# LEDS.net
KiCad netlist of a schematic drawn in Altium Designer
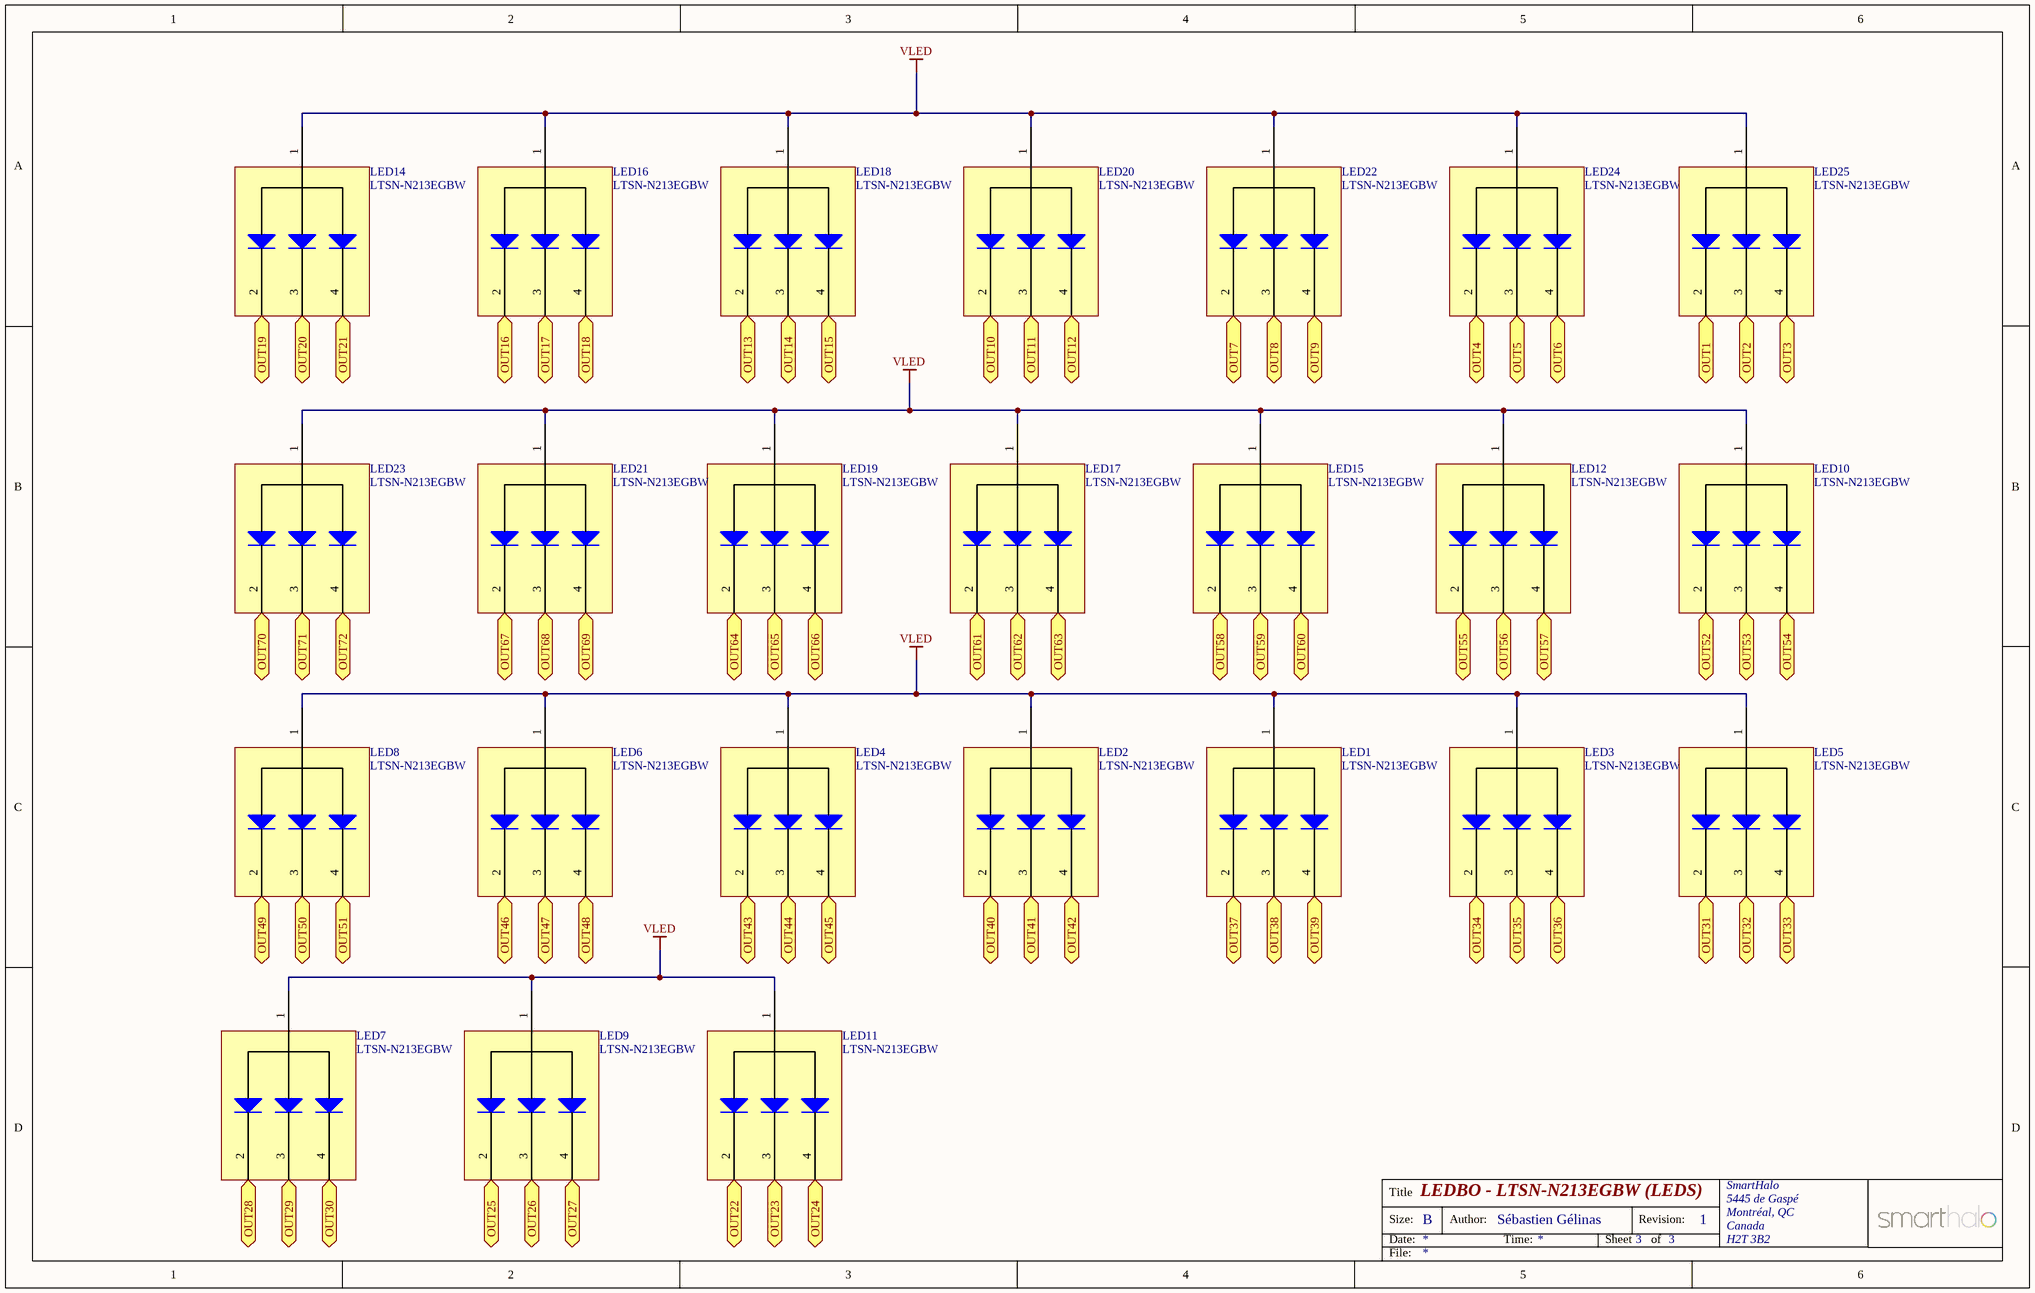
[diagram p0: LEDS.SchDoc]

(export (version "E")
  (design (tool "Eeschema 10.0.6"))
  (components
    (comp (ref "LED1")
      (value "LTSN-N213EGBW")
      (footprint "LTSN-N213EGBW")
      (description "LED SMD LTSN-N213EGBW")
      (fields (field (name "MANUFACTURER") "LiteOn"))
      (libsource (lib "SmartHalo") (part "LTSN-N213EGBW"))
    )
    (comp (ref "LED2")
      (value "LTSN-N213EGBW")
      (footprint "LTSN-N213EGBW")
      (description "LED SMD LTSN-N213EGBW")
      (fields (field (name "MANUFACTURER") "LiteOn"))
      (libsource (lib "SmartHalo") (part "LTSN-N213EGBW"))
    )
    (comp (ref "LED3")
      (value "LTSN-N213EGBW")
      (footprint "LTSN-N213EGBW")
      (description "LED SMD LTSN-N213EGBW")
      (fields (field (name "MANUFACTURER") "LiteOn"))
      (libsource (lib "SmartHalo") (part "LTSN-N213EGBW"))
    )
    (comp (ref "LED4")
      (value "LTSN-N213EGBW")
      (footprint "LTSN-N213EGBW")
      (description "LED SMD LTSN-N213EGBW")
      (fields (field (name "MANUFACTURER") "LiteOn"))
      (libsource (lib "SmartHalo") (part "LTSN-N213EGBW"))
    )
    (comp (ref "LED5")
      (value "LTSN-N213EGBW")
      (footprint "LTSN-N213EGBW")
      (description "LED SMD LTSN-N213EGBW")
      (fields (field (name "MANUFACTURER") "LiteOn"))
      (libsource (lib "SmartHalo") (part "LTSN-N213EGBW"))
    )
    (comp (ref "LED6")
      (value "LTSN-N213EGBW")
      (footprint "LTSN-N213EGBW")
      (description "LED SMD LTSN-N213EGBW")
      (fields (field (name "MANUFACTURER") "LiteOn"))
      (libsource (lib "SmartHalo") (part "LTSN-N213EGBW"))
    )
    (comp (ref "LED7")
      (value "LTSN-N213EGBW")
      (footprint "LTSN-N213EGBW")
      (description "LED SMD LTSN-N213EGBW")
      (fields (field (name "MANUFACTURER") "LiteOn"))
      (libsource (lib "SmartHalo") (part "LTSN-N213EGBW"))
    )
    (comp (ref "LED8")
      (value "LTSN-N213EGBW")
      (footprint "LTSN-N213EGBW")
      (description "LED SMD LTSN-N213EGBW")
      (fields (field (name "MANUFACTURER") "LiteOn"))
      (libsource (lib "SmartHalo") (part "LTSN-N213EGBW"))
    )
    (comp (ref "LED9")
      (value "LTSN-N213EGBW")
      (footprint "LTSN-N213EGBW")
      (description "LED SMD LTSN-N213EGBW")
      (fields (field (name "MANUFACTURER") "LiteOn"))
      (libsource (lib "SmartHalo") (part "LTSN-N213EGBW"))
    )
    (comp (ref "LED10")
      (value "LTSN-N213EGBW")
      (footprint "LTSN-N213EGBW")
      (description "LED SMD LTSN-N213EGBW")
      (fields (field (name "MANUFACTURER") "LiteOn"))
      (libsource (lib "SmartHalo") (part "LTSN-N213EGBW"))
    )
    (comp (ref "LED11")
      (value "LTSN-N213EGBW")
      (footprint "LTSN-N213EGBW")
      (description "LED SMD LTSN-N213EGBW")
      (fields (field (name "MANUFACTURER") "LiteOn"))
      (libsource (lib "SmartHalo") (part "LTSN-N213EGBW"))
    )
    (comp (ref "LED12")
      (value "LTSN-N213EGBW")
      (footprint "LTSN-N213EGBW")
      (description "LED SMD LTSN-N213EGBW")
      (fields (field (name "MANUFACTURER") "LiteOn"))
      (libsource (lib "SmartHalo") (part "LTSN-N213EGBW"))
    )
    (comp (ref "LED14")
      (value "LTSN-N213EGBW")
      (footprint "LTSN-N213EGBW")
      (description "LED SMD LTSN-N213EGBW")
      (fields (field (name "MANUFACTURER") "LiteOn"))
      (libsource (lib "SmartHalo") (part "LTSN-N213EGBW"))
    )
    (comp (ref "LED15")
      (value "LTSN-N213EGBW")
      (footprint "LTSN-N213EGBW")
      (description "LED SMD LTSN-N213EGBW")
      (fields (field (name "MANUFACTURER") "LiteOn"))
      (libsource (lib "SmartHalo") (part "LTSN-N213EGBW"))
    )
    (comp (ref "LED16")
      (value "LTSN-N213EGBW")
      (footprint "LTSN-N213EGBW")
      (description "LED SMD LTSN-N213EGBW")
      (fields (field (name "MANUFACTURER") "LiteOn"))
      (libsource (lib "SmartHalo") (part "LTSN-N213EGBW"))
    )
    (comp (ref "LED17")
      (value "LTSN-N213EGBW")
      (footprint "LTSN-N213EGBW")
      (description "LED SMD LTSN-N213EGBW")
      (fields (field (name "MANUFACTURER") "LiteOn"))
      (libsource (lib "SmartHalo") (part "LTSN-N213EGBW"))
    )
    (comp (ref "LED18")
      (value "LTSN-N213EGBW")
      (footprint "LTSN-N213EGBW")
      (description "LED SMD LTSN-N213EGBW")
      (fields (field (name "MANUFACTURER") "LiteOn"))
      (libsource (lib "SmartHalo") (part "LTSN-N213EGBW"))
    )
    (comp (ref "LED19")
      (value "LTSN-N213EGBW")
      (footprint "LTSN-N213EGBW")
      (description "LED SMD LTSN-N213EGBW")
      (fields (field (name "MANUFACTURER") "LiteOn"))
      (libsource (lib "SmartHalo") (part "LTSN-N213EGBW"))
    )
    (comp (ref "LED20")
      (value "LTSN-N213EGBW")
      (footprint "LTSN-N213EGBW")
      (description "LED SMD LTSN-N213EGBW")
      (fields (field (name "MANUFACTURER") "LiteOn"))
      (libsource (lib "SmartHalo") (part "LTSN-N213EGBW"))
    )
    (comp (ref "LED21")
      (value "LTSN-N213EGBW")
      (footprint "LTSN-N213EGBW")
      (description "LED SMD LTSN-N213EGBW")
      (fields (field (name "MANUFACTURER") "LiteOn"))
      (libsource (lib "SmartHalo") (part "LTSN-N213EGBW"))
    )
    (comp (ref "LED22")
      (value "LTSN-N213EGBW")
      (footprint "LTSN-N213EGBW")
      (description "LED SMD LTSN-N213EGBW")
      (fields (field (name "MANUFACTURER") "LiteOn"))
      (libsource (lib "SmartHalo") (part "LTSN-N213EGBW"))
    )
    (comp (ref "LED23")
      (value "LTSN-N213EGBW")
      (footprint "LTSN-N213EGBW")
      (description "LED SMD LTSN-N213EGBW")
      (fields (field (name "MANUFACTURER") "LiteOn"))
      (libsource (lib "SmartHalo") (part "LTSN-N213EGBW"))
    )
    (comp (ref "LED24")
      (value "LTSN-N213EGBW")
      (footprint "LTSN-N213EGBW")
      (description "LED SMD LTSN-N213EGBW")
      (fields (field (name "MANUFACTURER") "LiteOn"))
      (libsource (lib "SmartHalo") (part "LTSN-N213EGBW"))
    )
    (comp (ref "LED25")
      (value "LTSN-N213EGBW")
      (footprint "LTSN-N213EGBW")
      (description "LED SMD LTSN-N213EGBW")
      (fields (field (name "MANUFACTURER") "LiteOn"))
      (libsource (lib "SmartHalo") (part "LTSN-N213EGBW"))
    )
  )
  (nets
    (net (code "1") (name "/OUT1") (class "Default")
      (node (ref "LED25") (pin "2") (pinfunction "Cathode_Red_2") (pintype "passive"))
    )
    (net (code "2") (name "/OUT2") (class "Default")
      (node (ref "LED25") (pin "3") (pinfunction "Cathode_Green_3") (pintype "passive"))
    )
    (net (code "3") (name "/OUT3") (class "Default")
      (node (ref "LED25") (pin "4") (pinfunction "Cathode_Blue_4") (pintype "passive"))
    )
    (net (code "4") (name "/OUT4") (class "Default")
      (node (ref "LED24") (pin "2") (pinfunction "Cathode_Red_2") (pintype "passive"))
    )
    (net (code "5") (name "/OUT5") (class "Default")
      (node (ref "LED24") (pin "3") (pinfunction "Cathode_Green_3") (pintype "passive"))
    )
    (net (code "6") (name "/OUT6") (class "Default")
      (node (ref "LED24") (pin "4") (pinfunction "Cathode_Blue_4") (pintype "passive"))
    )
    (net (code "7") (name "/OUT7") (class "Default")
      (node (ref "LED22") (pin "2") (pinfunction "Cathode_Red_2") (pintype "passive"))
    )
    (net (code "8") (name "/OUT8") (class "Default")
      (node (ref "LED22") (pin "3") (pinfunction "Cathode_Green_3") (pintype "passive"))
    )
    (net (code "9") (name "/OUT9") (class "Default")
      (node (ref "LED22") (pin "4") (pinfunction "Cathode_Blue_4") (pintype "passive"))
    )
    (net (code "10") (name "/OUT10") (class "Default")
      (node (ref "LED20") (pin "2") (pinfunction "Cathode_Red_2") (pintype "passive"))
    )
    (net (code "11") (name "/OUT11") (class "Default")
      (node (ref "LED20") (pin "3") (pinfunction "Cathode_Green_3") (pintype "passive"))
    )
    (net (code "12") (name "/OUT12") (class "Default")
      (node (ref "LED20") (pin "4") (pinfunction "Cathode_Blue_4") (pintype "passive"))
    )
    (net (code "13") (name "/OUT13") (class "Default")
      (node (ref "LED18") (pin "2") (pinfunction "Cathode_Red_2") (pintype "passive"))
    )
    (net (code "14") (name "/OUT14") (class "Default")
      (node (ref "LED18") (pin "3") (pinfunction "Cathode_Green_3") (pintype "passive"))
    )
    (net (code "15") (name "/OUT15") (class "Default")
      (node (ref "LED18") (pin "4") (pinfunction "Cathode_Blue_4") (pintype "passive"))
    )
    (net (code "16") (name "/OUT16") (class "Default")
      (node (ref "LED16") (pin "2") (pinfunction "Cathode_Red_2") (pintype "passive"))
    )
    (net (code "17") (name "/OUT17") (class "Default")
      (node (ref "LED16") (pin "3") (pinfunction "Cathode_Green_3") (pintype "passive"))
    )
    (net (code "18") (name "/OUT18") (class "Default")
      (node (ref "LED16") (pin "4") (pinfunction "Cathode_Blue_4") (pintype "passive"))
    )
    (net (code "19") (name "/OUT19") (class "Default")
      (node (ref "LED14") (pin "2") (pinfunction "Cathode_Red_2") (pintype "passive"))
    )
    (net (code "20") (name "/OUT20") (class "Default")
      (node (ref "LED14") (pin "3") (pinfunction "Cathode_Green_3") (pintype "passive"))
    )
    (net (code "21") (name "/OUT21") (class "Default")
      (node (ref "LED14") (pin "4") (pinfunction "Cathode_Blue_4") (pintype "passive"))
    )
    (net (code "22") (name "/OUT22") (class "Default")
      (node (ref "LED11") (pin "2") (pinfunction "Cathode_Red_2") (pintype "passive"))
    )
    (net (code "23") (name "/OUT23") (class "Default")
      (node (ref "LED11") (pin "3") (pinfunction "Cathode_Green_3") (pintype "passive"))
    )
    (net (code "24") (name "/OUT24") (class "Default")
      (node (ref "LED11") (pin "4") (pinfunction "Cathode_Blue_4") (pintype "passive"))
    )
    (net (code "25") (name "/OUT25") (class "Default")
      (node (ref "LED9") (pin "2") (pinfunction "Cathode_Red_2") (pintype "passive"))
    )
    (net (code "26") (name "/OUT26") (class "Default")
      (node (ref "LED9") (pin "3") (pinfunction "Cathode_Green_3") (pintype "passive"))
    )
    (net (code "27") (name "/OUT27") (class "Default")
      (node (ref "LED9") (pin "4") (pinfunction "Cathode_Blue_4") (pintype "passive"))
    )
    (net (code "28") (name "/OUT28") (class "Default")
      (node (ref "LED7") (pin "2") (pinfunction "Cathode_Red_2") (pintype "passive"))
    )
    (net (code "29") (name "/OUT29") (class "Default")
      (node (ref "LED7") (pin "3") (pinfunction "Cathode_Green_3") (pintype "passive"))
    )
    (net (code "30") (name "/OUT30") (class "Default")
      (node (ref "LED7") (pin "4") (pinfunction "Cathode_Blue_4") (pintype "passive"))
    )
    (net (code "31") (name "/OUT31") (class "Default")
      (node (ref "LED5") (pin "2") (pinfunction "Cathode_Red_2") (pintype "passive"))
    )
    (net (code "32") (name "/OUT32") (class "Default")
      (node (ref "LED5") (pin "3") (pinfunction "Cathode_Green_3") (pintype "passive"))
    )
    (net (code "33") (name "/OUT33") (class "Default")
      (node (ref "LED5") (pin "4") (pinfunction "Cathode_Blue_4") (pintype "passive"))
    )
    (net (code "34") (name "/OUT34") (class "Default")
      (node (ref "LED3") (pin "2") (pinfunction "Cathode_Red_2") (pintype "passive"))
    )
    (net (code "35") (name "/OUT35") (class "Default")
      (node (ref "LED3") (pin "3") (pinfunction "Cathode_Green_3") (pintype "passive"))
    )
    (net (code "36") (name "/OUT36") (class "Default")
      (node (ref "LED3") (pin "4") (pinfunction "Cathode_Blue_4") (pintype "passive"))
    )
    (net (code "37") (name "/OUT37") (class "Default")
      (node (ref "LED1") (pin "2") (pinfunction "Cathode_Red_2") (pintype "passive"))
    )
    (net (code "38") (name "/OUT38") (class "Default")
      (node (ref "LED1") (pin "3") (pinfunction "Cathode_Green_3") (pintype "passive"))
    )
    (net (code "39") (name "/OUT39") (class "Default")
      (node (ref "LED1") (pin "4") (pinfunction "Cathode_Blue_4") (pintype "passive"))
    )
    (net (code "40") (name "/OUT40") (class "Default")
      (node (ref "LED2") (pin "2") (pinfunction "Cathode_Red_2") (pintype "passive"))
    )
    (net (code "41") (name "/OUT41") (class "Default")
      (node (ref "LED2") (pin "3") (pinfunction "Cathode_Green_3") (pintype "passive"))
    )
    (net (code "42") (name "/OUT42") (class "Default")
      (node (ref "LED2") (pin "4") (pinfunction "Cathode_Blue_4") (pintype "passive"))
    )
    (net (code "43") (name "/OUT43") (class "Default")
      (node (ref "LED4") (pin "2") (pinfunction "Cathode_Red_2") (pintype "passive"))
    )
    (net (code "44") (name "/OUT44") (class "Default")
      (node (ref "LED4") (pin "3") (pinfunction "Cathode_Green_3") (pintype "passive"))
    )
    (net (code "45") (name "/OUT45") (class "Default")
      (node (ref "LED4") (pin "4") (pinfunction "Cathode_Blue_4") (pintype "passive"))
    )
    (net (code "46") (name "/OUT46") (class "Default")
      (node (ref "LED6") (pin "2") (pinfunction "Cathode_Red_2") (pintype "passive"))
    )
    (net (code "47") (name "/OUT47") (class "Default")
      (node (ref "LED6") (pin "3") (pinfunction "Cathode_Green_3") (pintype "passive"))
    )
    (net (code "48") (name "/OUT48") (class "Default")
      (node (ref "LED6") (pin "4") (pinfunction "Cathode_Blue_4") (pintype "passive"))
    )
    (net (code "49") (name "/OUT49") (class "Default")
      (node (ref "LED8") (pin "2") (pinfunction "Cathode_Red_2") (pintype "passive"))
    )
    (net (code "50") (name "/OUT50") (class "Default")
      (node (ref "LED8") (pin "3") (pinfunction "Cathode_Green_3") (pintype "passive"))
    )
    (net (code "51") (name "/OUT51") (class "Default")
      (node (ref "LED8") (pin "4") (pinfunction "Cathode_Blue_4") (pintype "passive"))
    )
    (net (code "52") (name "/OUT52") (class "Default")
      (node (ref "LED10") (pin "2") (pinfunction "Cathode_Red_2") (pintype "passive"))
    )
    (net (code "53") (name "/OUT53") (class "Default")
      (node (ref "LED10") (pin "3") (pinfunction "Cathode_Green_3") (pintype "passive"))
    )
    (net (code "54") (name "/OUT54") (class "Default")
      (node (ref "LED10") (pin "4") (pinfunction "Cathode_Blue_4") (pintype "passive"))
    )
    (net (code "55") (name "/OUT55") (class "Default")
      (node (ref "LED12") (pin "2") (pinfunction "Cathode_Red_2") (pintype "passive"))
    )
    (net (code "56") (name "/OUT56") (class "Default")
      (node (ref "LED12") (pin "3") (pinfunction "Cathode_Green_3") (pintype "passive"))
    )
    (net (code "57") (name "/OUT57") (class "Default")
      (node (ref "LED12") (pin "4") (pinfunction "Cathode_Blue_4") (pintype "passive"))
    )
    (net (code "58") (name "/OUT58") (class "Default")
      (node (ref "LED15") (pin "2") (pinfunction "Cathode_Red_2") (pintype "passive"))
    )
    (net (code "59") (name "/OUT59") (class "Default")
      (node (ref "LED15") (pin "3") (pinfunction "Cathode_Green_3") (pintype "passive"))
    )
    (net (code "60") (name "/OUT60") (class "Default")
      (node (ref "LED15") (pin "4") (pinfunction "Cathode_Blue_4") (pintype "passive"))
    )
    (net (code "61") (name "/OUT61") (class "Default")
      (node (ref "LED17") (pin "2") (pinfunction "Cathode_Red_2") (pintype "passive"))
    )
    (net (code "62") (name "/OUT62") (class "Default")
      (node (ref "LED17") (pin "3") (pinfunction "Cathode_Green_3") (pintype "passive"))
    )
    (net (code "63") (name "/OUT63") (class "Default")
      (node (ref "LED17") (pin "4") (pinfunction "Cathode_Blue_4") (pintype "passive"))
    )
    (net (code "64") (name "/OUT64") (class "Default")
      (node (ref "LED19") (pin "2") (pinfunction "Cathode_Red_2") (pintype "passive"))
    )
    (net (code "65") (name "/OUT65") (class "Default")
      (node (ref "LED19") (pin "3") (pinfunction "Cathode_Green_3") (pintype "passive"))
    )
    (net (code "66") (name "/OUT66") (class "Default")
      (node (ref "LED19") (pin "4") (pinfunction "Cathode_Blue_4") (pintype "passive"))
    )
    (net (code "67") (name "/OUT67") (class "Default")
      (node (ref "LED21") (pin "2") (pinfunction "Cathode_Red_2") (pintype "passive"))
    )
    (net (code "68") (name "/OUT68") (class "Default")
      (node (ref "LED21") (pin "3") (pinfunction "Cathode_Green_3") (pintype "passive"))
    )
    (net (code "69") (name "/OUT69") (class "Default")
      (node (ref "LED21") (pin "4") (pinfunction "Cathode_Blue_4") (pintype "passive"))
    )
    (net (code "70") (name "/OUT70") (class "Default")
      (node (ref "LED23") (pin "2") (pinfunction "Cathode_Red_2") (pintype "passive"))
    )
    (net (code "71") (name "/OUT71") (class "Default")
      (node (ref "LED23") (pin "3") (pinfunction "Cathode_Green_3") (pintype "passive"))
    )
    (net (code "72") (name "/OUT72") (class "Default")
      (node (ref "LED23") (pin "4") (pinfunction "Cathode_Blue_4") (pintype "passive"))
    )
    (net (code "73") (name "VLED") (class "Default")
      (node (ref "LED1") (pin "1") (pinfunction "Anode_1") (pintype "passive"))
      (node (ref "LED10") (pin "1") (pinfunction "Anode_1") (pintype "passive"))
      (node (ref "LED11") (pin "1") (pinfunction "Anode_1") (pintype "passive"))
      (node (ref "LED12") (pin "1") (pinfunction "Anode_1") (pintype "passive"))
      (node (ref "LED14") (pin "1") (pinfunction "Anode_1") (pintype "passive"))
      (node (ref "LED15") (pin "1") (pinfunction "Anode_1") (pintype "passive"))
      (node (ref "LED16") (pin "1") (pinfunction "Anode_1") (pintype "passive"))
      (node (ref "LED17") (pin "1") (pinfunction "Anode_1") (pintype "passive"))
      (node (ref "LED18") (pin "1") (pinfunction "Anode_1") (pintype "passive"))
      (node (ref "LED19") (pin "1") (pinfunction "Anode_1") (pintype "passive"))
      (node (ref "LED2") (pin "1") (pinfunction "Anode_1") (pintype "passive"))
      (node (ref "LED20") (pin "1") (pinfunction "Anode_1") (pintype "passive"))
      (node (ref "LED21") (pin "1") (pinfunction "Anode_1") (pintype "passive"))
      (node (ref "LED22") (pin "1") (pinfunction "Anode_1") (pintype "passive"))
      (node (ref "LED23") (pin "1") (pinfunction "Anode_1") (pintype "passive"))
      (node (ref "LED24") (pin "1") (pinfunction "Anode_1") (pintype "passive"))
      (node (ref "LED25") (pin "1") (pinfunction "Anode_1") (pintype "passive"))
      (node (ref "LED3") (pin "1") (pinfunction "Anode_1") (pintype "passive"))
      (node (ref "LED4") (pin "1") (pinfunction "Anode_1") (pintype "passive"))
      (node (ref "LED5") (pin "1") (pinfunction "Anode_1") (pintype "passive"))
      (node (ref "LED6") (pin "1") (pinfunction "Anode_1") (pintype "passive"))
      (node (ref "LED7") (pin "1") (pinfunction "Anode_1") (pintype "passive"))
      (node (ref "LED8") (pin "1") (pinfunction "Anode_1") (pintype "passive"))
      (node (ref "LED9") (pin "1") (pinfunction "Anode_1") (pintype "passive"))
    )
  )
)
